# IMU-Measurement-and-Transmission-Module.net
KiCad netlist of a schematic drawn in EAGLE
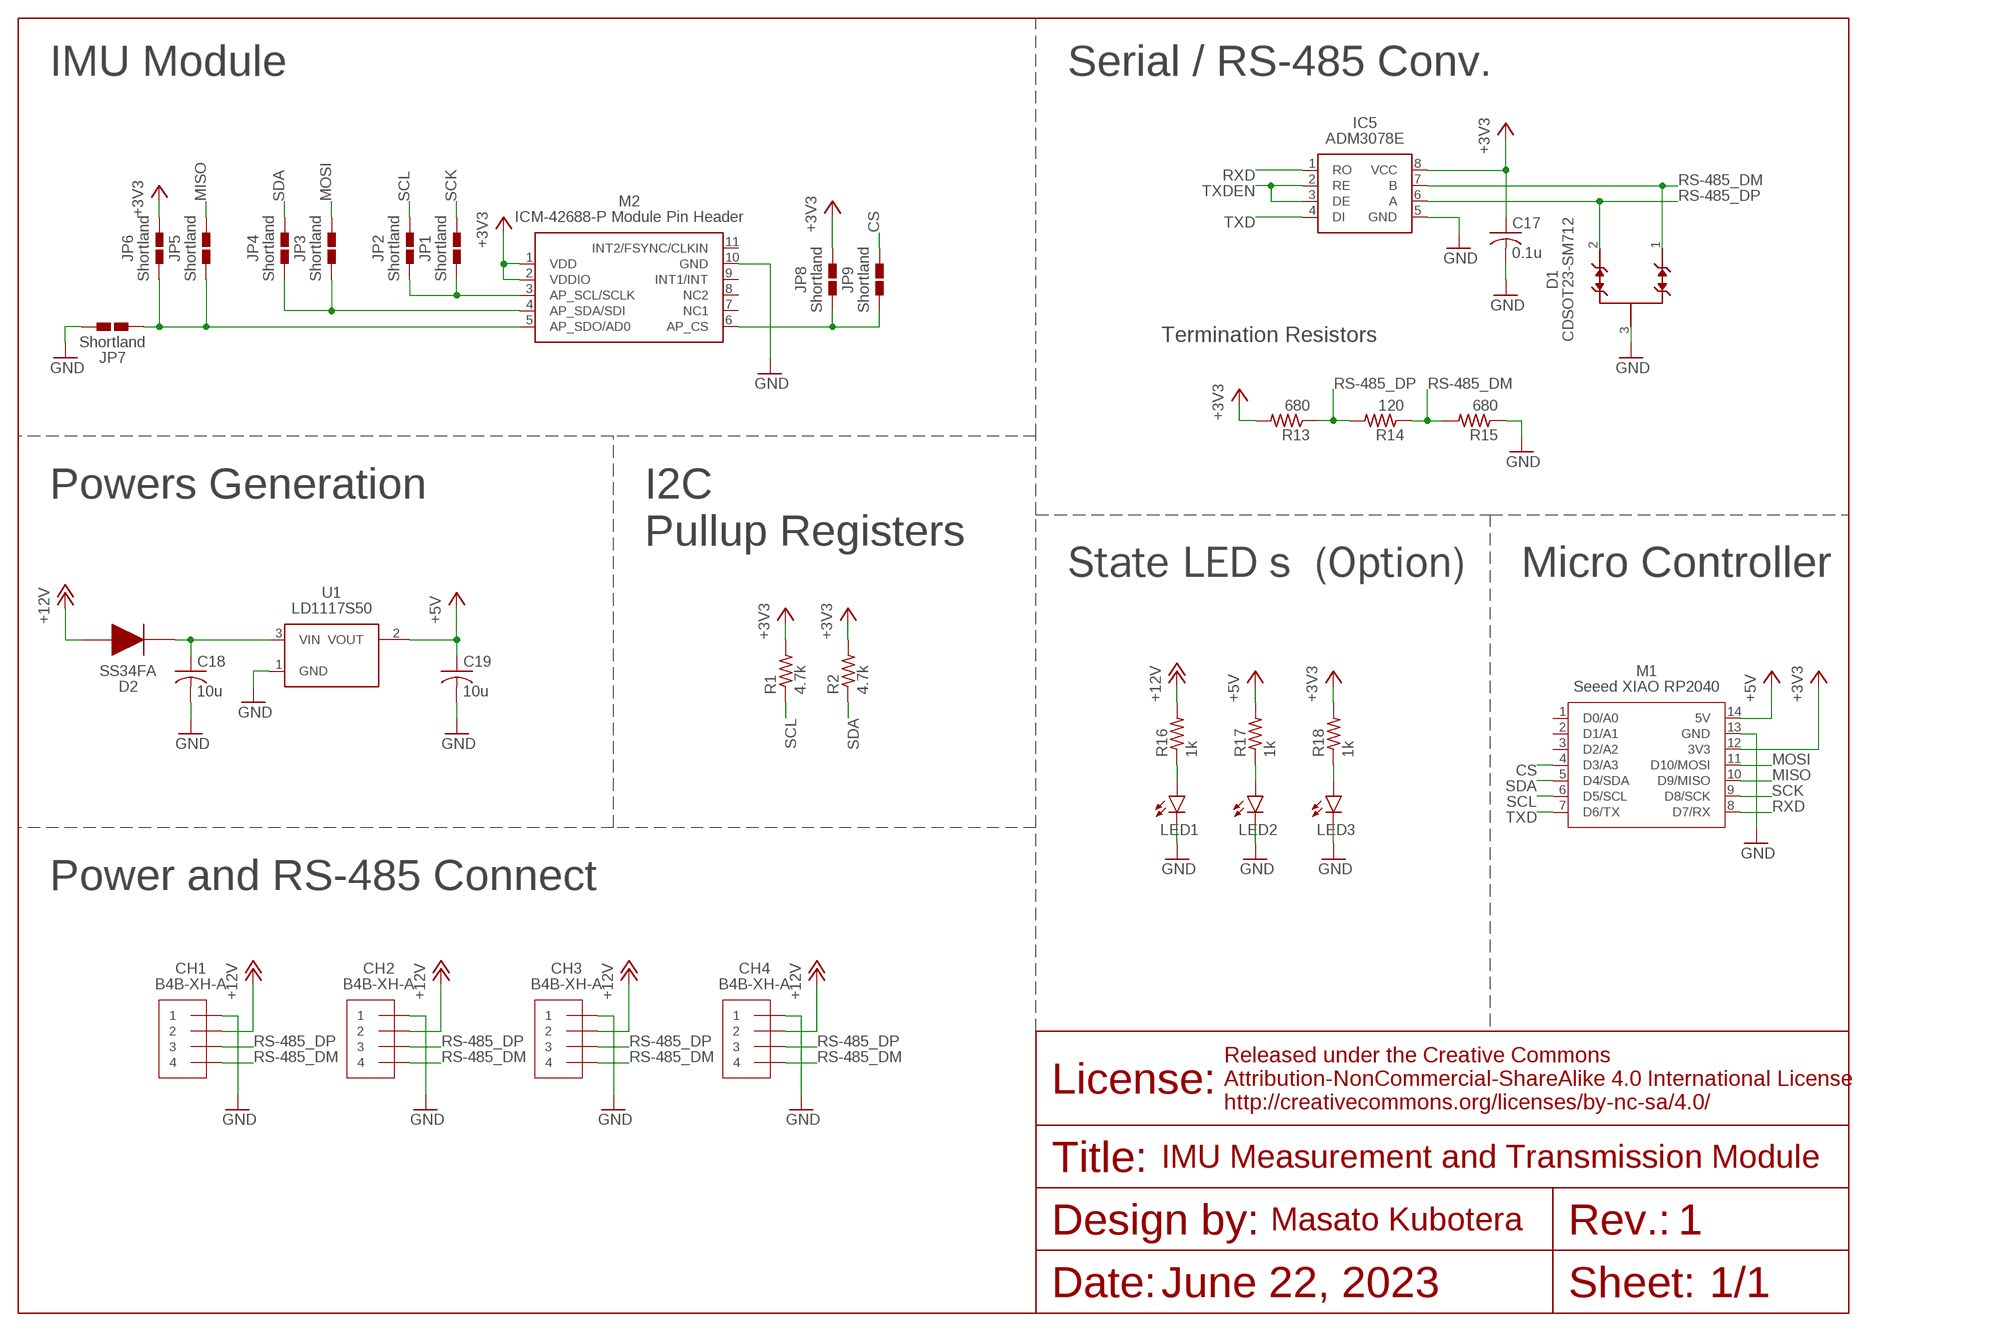
[diagram p0: schematic, sheet 1]

(export (version "E")
  (design (tool "Eeschema 10.0.6"))
  (components
    (comp (ref "C17")
      (value "0.1u")
      (footprint "eagle-import:C0603")
      (libsource (lib "eagle-import") (part "C-USC0603"))
    )
    (comp (ref "C18")
      (value "10u")
      (footprint "eagle-import:C0603")
      (libsource (lib "eagle-import") (part "C-USC0603"))
    )
    (comp (ref "C19")
      (value "10u")
      (footprint "eagle-import:C0603")
      (libsource (lib "eagle-import") (part "C-USC0603"))
    )
    (comp (ref "CH1")
      (value "B4B-XH-A")
      (footprint "eagle-import:B4B-XH-A")
      (libsource (lib "eagle-import") (part "B4B-XH-A"))
    )
    (comp (ref "CH2")
      (value "B4B-XH-A")
      (footprint "eagle-import:B4B-XH-A")
      (libsource (lib "eagle-import") (part "B4B-XH-A"))
    )
    (comp (ref "CH3")
      (value "B4B-XH-A")
      (footprint "eagle-import:B4B-XH-A")
      (libsource (lib "eagle-import") (part "B4B-XH-A"))
    )
    (comp (ref "CH4")
      (value "B4B-XH-A")
      (footprint "eagle-import:B4B-XH-A")
      (libsource (lib "eagle-import") (part "B4B-XH-A"))
    )
    (comp (ref "D1")
      (value "CDSOT23-SM712")
      (footprint "eagle-import:SOT-23-3")
      (libsource (lib "eagle-import") (part "CDSOT23-SM712"))
    )
    (comp (ref "D2")
      (value "SS34FA")
      (footprint "eagle-import:SS34FA")
      (libsource (lib "eagle-import") (part "SS34FA"))
    )
    (comp (ref "IC5")
      (value "ADM3078E")
      (footprint "eagle-import:ADM3078E")
      (libsource (lib "eagle-import") (part "ADM3078E"))
    )
    (comp (ref "JP1")
      (value "SHORTLAND")
      (footprint "eagle-import:SHORTLAND")
      (libsource (lib "eagle-import") (part "SHORTLAND"))
    )
    (comp (ref "JP2")
      (value "SHORTLAND")
      (footprint "eagle-import:SHORTLAND")
      (libsource (lib "eagle-import") (part "SHORTLAND"))
    )
    (comp (ref "JP3")
      (value "SHORTLAND")
      (footprint "eagle-import:SHORTLAND")
      (libsource (lib "eagle-import") (part "SHORTLAND"))
    )
    (comp (ref "JP4")
      (value "SHORTLAND")
      (footprint "eagle-import:SHORTLAND")
      (libsource (lib "eagle-import") (part "SHORTLAND"))
    )
    (comp (ref "JP5")
      (value "SHORTLAND")
      (footprint "eagle-import:SHORTLAND")
      (libsource (lib "eagle-import") (part "SHORTLAND"))
    )
    (comp (ref "JP6")
      (value "SHORTLAND")
      (footprint "eagle-import:SHORTLAND")
      (libsource (lib "eagle-import") (part "SHORTLAND"))
    )
    (comp (ref "JP7")
      (value "SHORTLAND")
      (footprint "eagle-import:SHORTLAND")
      (libsource (lib "eagle-import") (part "SHORTLAND"))
    )
    (comp (ref "JP8")
      (value "SHORTLAND")
      (footprint "eagle-import:SHORTLAND")
      (libsource (lib "eagle-import") (part "SHORTLAND"))
    )
    (comp (ref "JP9")
      (value "SHORTLAND")
      (footprint "eagle-import:SHORTLAND")
      (libsource (lib "eagle-import") (part "SHORTLAND"))
    )
    (comp (ref "LED1")
      (value "LEDSML0603")
      (footprint "eagle-import:SML0603")
      (libsource (lib "eagle-import") (part "LEDSML0603"))
    )
    (comp (ref "LED2")
      (value "LEDSML0603")
      (footprint "eagle-import:SML0603")
      (libsource (lib "eagle-import") (part "LEDSML0603"))
    )
    (comp (ref "LED3")
      (value "LEDSML0603")
      (footprint "eagle-import:SML0603")
      (libsource (lib "eagle-import") (part "LEDSML0603"))
    )
    (comp (ref "M1")
      (value "SEEED_XIAO_RP2040_HOLE")
      (footprint "eagle-import:SEEED_XIAO_HOLE")
      (libsource (lib "eagle-import") (part "SEEED_XIAO_RP2040_HOLE"))
    )
    (comp (ref "M2")
      (value "ICM-42688-P-MODULE-PINHEADER")
      (footprint "eagle-import:ICM-42688-P-MODULE-PINHEADER")
      (libsource (lib "eagle-import") (part "ICM-42688-P-MODULE-PINHEADER"))
    )
    (comp (ref "R1")
      (value "4.7k")
      (footprint "eagle-import:R0603")
      (libsource (lib "eagle-import") (part "R-US_R0603"))
    )
    (comp (ref "R2")
      (value "4.7k")
      (footprint "eagle-import:R0603")
      (libsource (lib "eagle-import") (part "R-US_R0603"))
    )
    (comp (ref "R13")
      (value "680")
      (footprint "eagle-import:R0603")
      (libsource (lib "eagle-import") (part "R-US_R0603"))
    )
    (comp (ref "R14")
      (value "120")
      (footprint "eagle-import:R0603")
      (libsource (lib "eagle-import") (part "R-US_R0603"))
    )
    (comp (ref "R15")
      (value "680")
      (footprint "eagle-import:R0603")
      (libsource (lib "eagle-import") (part "R-US_R0603"))
    )
    (comp (ref "R16")
      (value "1k")
      (footprint "eagle-import:R0603")
      (libsource (lib "eagle-import") (part "R-US_R0603"))
    )
    (comp (ref "R17")
      (value "1k")
      (footprint "eagle-import:R0603")
      (libsource (lib "eagle-import") (part "R-US_R0603"))
    )
    (comp (ref "R18")
      (value "1k")
      (footprint "eagle-import:R0603")
      (libsource (lib "eagle-import") (part "R-US_R0603"))
    )
    (comp (ref "U1")
      (value "LD1117S50")
      (footprint "eagle-import:SOT-223")
      (libsource (lib "eagle-import") (part "LD1117S50"))
    )
  )
  (nets
    (net (code "1") (name "+3V3") (class "Default")
      (node (ref "C17") (pin "1") (pinfunction "1_1") (pintype "passive"))
      (node (ref "IC5") (pin "8") (pinfunction "VCC_8") (pintype "bidirectional"))
      (node (ref "JP6") (pin "2") (pinfunction "2_2") (pintype "bidirectional"))
      (node (ref "JP8") (pin "2") (pinfunction "2_2") (pintype "bidirectional"))
      (node (ref "M1") (pin "12") (pinfunction "3V3_12") (pintype "bidirectional"))
      (node (ref "M2") (pin "1") (pinfunction "VDD_1") (pintype "bidirectional"))
      (node (ref "M2") (pin "2") (pinfunction "VDDIO_2") (pintype "bidirectional"))
      (node (ref "R1") (pin "2") (pinfunction "2_2") (pintype "passive"))
      (node (ref "R13") (pin "2") (pinfunction "2_2") (pintype "passive"))
      (node (ref "R18") (pin "2") (pinfunction "2_2") (pintype "passive"))
      (node (ref "R2") (pin "2") (pinfunction "2_2") (pintype "passive"))
    )
    (net (code "2") (name "+5V") (class "Default")
      (node (ref "C19") (pin "1") (pinfunction "1_1") (pintype "passive"))
      (node (ref "M1") (pin "14") (pinfunction "5V_14") (pintype "bidirectional"))
      (node (ref "R17") (pin "2") (pinfunction "2_2") (pintype "passive"))
      (node (ref "U1") (pin "2") (pinfunction "VOUT_2") (pintype "bidirectional"))
    )
    (net (code "3") (name "+12V") (class "Default")
      (node (ref "CH1") (pin "2") (pinfunction "2_2") (pintype "bidirectional"))
      (node (ref "CH2") (pin "2") (pinfunction "2_2") (pintype "bidirectional"))
      (node (ref "CH3") (pin "2") (pinfunction "2_2") (pintype "bidirectional"))
      (node (ref "CH4") (pin "2") (pinfunction "2_2") (pintype "bidirectional"))
      (node (ref "D2") (pin "2") (pinfunction "2_2") (pintype "bidirectional"))
      (node (ref "R16") (pin "2") (pinfunction "2_2") (pintype "passive"))
    )
    (net (code "4") (name "/CS") (class "Default")
      (node (ref "JP9") (pin "2") (pinfunction "2_2") (pintype "bidirectional"))
      (node (ref "M1") (pin "4") (pinfunction "D3/A3_4") (pintype "bidirectional"))
    )
    (net (code "5") (name "/MISO") (class "Default")
      (node (ref "JP5") (pin "2") (pinfunction "2_2") (pintype "bidirectional"))
      (node (ref "M1") (pin "10") (pinfunction "D9/MISO_10") (pintype "bidirectional"))
    )
    (net (code "6") (name "/MOSI") (class "Default")
      (node (ref "JP3") (pin "2") (pinfunction "2_2") (pintype "bidirectional"))
      (node (ref "M1") (pin "11") (pinfunction "D10/MOSI_11") (pintype "bidirectional"))
    )
    (net (code "7") (name "/RS-485_DM") (class "Default")
      (node (ref "CH1") (pin "4") (pinfunction "4_4") (pintype "bidirectional"))
      (node (ref "CH2") (pin "4") (pinfunction "4_4") (pintype "bidirectional"))
      (node (ref "CH3") (pin "4") (pinfunction "4_4") (pintype "bidirectional"))
      (node (ref "CH4") (pin "4") (pinfunction "4_4") (pintype "bidirectional"))
      (node (ref "D1") (pin "1") (pinfunction "1_1") (pintype "bidirectional"))
      (node (ref "IC5") (pin "7") (pinfunction "B_7") (pintype "bidirectional"))
      (node (ref "R14") (pin "1") (pinfunction "1_1") (pintype "passive"))
      (node (ref "R15") (pin "2") (pinfunction "2_2") (pintype "passive"))
    )
    (net (code "8") (name "/RS-485_DP") (class "Default")
      (node (ref "CH1") (pin "3") (pinfunction "3_3") (pintype "bidirectional"))
      (node (ref "CH2") (pin "3") (pinfunction "3_3") (pintype "bidirectional"))
      (node (ref "CH3") (pin "3") (pinfunction "3_3") (pintype "bidirectional"))
      (node (ref "CH4") (pin "3") (pinfunction "3_3") (pintype "bidirectional"))
      (node (ref "D1") (pin "2") (pinfunction "2_2") (pintype "bidirectional"))
      (node (ref "IC5") (pin "6") (pinfunction "A_6") (pintype "bidirectional"))
      (node (ref "R13") (pin "1") (pinfunction "1_1") (pintype "passive"))
      (node (ref "R14") (pin "2") (pinfunction "2_2") (pintype "passive"))
    )
    (net (code "9") (name "/RXD") (class "Default")
      (node (ref "IC5") (pin "1") (pinfunction "RO_1") (pintype "bidirectional"))
      (node (ref "M1") (pin "8") (pinfunction "D7/RX_8") (pintype "bidirectional"))
    )
    (net (code "10") (name "/SCK") (class "Default")
      (node (ref "JP1") (pin "2") (pinfunction "2_2") (pintype "bidirectional"))
      (node (ref "M1") (pin "9") (pinfunction "D8/SCK_9") (pintype "bidirectional"))
    )
    (net (code "11") (name "/SCL") (class "Default")
      (node (ref "JP2") (pin "2") (pinfunction "2_2") (pintype "bidirectional"))
      (node (ref "M1") (pin "6") (pinfunction "D5/SCL_6") (pintype "bidirectional"))
      (node (ref "R1") (pin "1") (pinfunction "1_1") (pintype "passive"))
    )
    (net (code "12") (name "/SDA") (class "Default")
      (node (ref "JP4") (pin "2") (pinfunction "2_2") (pintype "bidirectional"))
      (node (ref "M1") (pin "5") (pinfunction "D4/SDA_5") (pintype "bidirectional"))
      (node (ref "R2") (pin "1") (pinfunction "1_1") (pintype "passive"))
    )
    (net (code "13") (name "/TXD") (class "Default")
      (node (ref "IC5") (pin "4") (pinfunction "DI_4") (pintype "bidirectional"))
      (node (ref "M1") (pin "7") (pinfunction "D6/TX_7") (pintype "bidirectional"))
    )
    (net (code "14") (name "/TXDEN") (class "Default")
      (node (ref "IC5") (pin "2") (pinfunction "RE_2") (pintype "bidirectional"))
      (node (ref "IC5") (pin "3") (pinfunction "DE_3") (pintype "bidirectional"))
    )
    (net (code "15") (name "GND") (class "Default")
      (node (ref "C17") (pin "2") (pinfunction "2_2") (pintype "passive"))
      (node (ref "C18") (pin "2") (pinfunction "2_2") (pintype "passive"))
      (node (ref "C19") (pin "2") (pinfunction "2_2") (pintype "passive"))
      (node (ref "CH1") (pin "1") (pinfunction "1_1") (pintype "bidirectional"))
      (node (ref "CH2") (pin "1") (pinfunction "1_1") (pintype "bidirectional"))
      (node (ref "CH3") (pin "1") (pinfunction "1_1") (pintype "bidirectional"))
      (node (ref "CH4") (pin "1") (pinfunction "1_1") (pintype "bidirectional"))
      (node (ref "D1") (pin "3") (pinfunction "3_3") (pintype "bidirectional"))
      (node (ref "IC5") (pin "5") (pinfunction "GND_5") (pintype "bidirectional"))
      (node (ref "JP7") (pin "2") (pinfunction "2_2") (pintype "bidirectional"))
      (node (ref "LED1") (pin "C") (pinfunction "C_C") (pintype "passive"))
      (node (ref "LED2") (pin "C") (pinfunction "C_C") (pintype "passive"))
      (node (ref "LED3") (pin "C") (pinfunction "C_C") (pintype "passive"))
      (node (ref "M1") (pin "13") (pinfunction "GND_13") (pintype "bidirectional"))
      (node (ref "M2") (pin "10") (pinfunction "GND_10") (pintype "bidirectional"))
      (node (ref "R15") (pin "1") (pinfunction "1_1") (pintype "passive"))
      (node (ref "U1") (pin "1") (pinfunction "GND_1") (pintype "bidirectional"))
    )
    (net (code "16") (name "Net-(LED1-PadA)") (class "Default")
      (node (ref "LED1") (pin "A") (pinfunction "A_A") (pintype "passive"))
      (node (ref "R16") (pin "1") (pinfunction "1_1") (pintype "passive"))
    )
    (net (code "17") (name "Net-(LED2-PadA)") (class "Default")
      (node (ref "LED2") (pin "A") (pinfunction "A_A") (pintype "passive"))
      (node (ref "R17") (pin "1") (pinfunction "1_1") (pintype "passive"))
    )
    (net (code "18") (name "Net-(LED3-PadA)") (class "Default")
      (node (ref "LED3") (pin "A") (pinfunction "A_A") (pintype "passive"))
      (node (ref "R18") (pin "1") (pinfunction "1_1") (pintype "passive"))
    )
    (net (code "19") (name "Net-(M2-AP_CS)") (class "Default")
      (node (ref "JP8") (pin "1") (pinfunction "1_1") (pintype "bidirectional"))
      (node (ref "JP9") (pin "1") (pinfunction "1_1") (pintype "bidirectional"))
      (node (ref "M2") (pin "6") (pinfunction "AP_CS_6") (pintype "bidirectional"))
    )
    (net (code "20") (name "Net-(M2-AP_SCL{slash}SCLK)") (class "Default")
      (node (ref "JP1") (pin "1") (pinfunction "1_1") (pintype "bidirectional"))
      (node (ref "JP2") (pin "1") (pinfunction "1_1") (pintype "bidirectional"))
      (node (ref "M2") (pin "3") (pinfunction "AP_SCL/SCLK_3") (pintype "bidirectional"))
    )
    (net (code "21") (name "Net-(M2-AP_SDA{slash}SDI)") (class "Default")
      (node (ref "JP3") (pin "1") (pinfunction "1_1") (pintype "bidirectional"))
      (node (ref "JP4") (pin "1") (pinfunction "1_1") (pintype "bidirectional"))
      (node (ref "M2") (pin "4") (pinfunction "AP_SDA/SDI_4") (pintype "bidirectional"))
    )
    (net (code "22") (name "Net-(M2-AP_SDO{slash}AD0)") (class "Default")
      (node (ref "JP5") (pin "1") (pinfunction "1_1") (pintype "bidirectional"))
      (node (ref "JP6") (pin "1") (pinfunction "1_1") (pintype "bidirectional"))
      (node (ref "JP7") (pin "1") (pinfunction "1_1") (pintype "bidirectional"))
      (node (ref "M2") (pin "5") (pinfunction "AP_SDO/AD0_5") (pintype "bidirectional"))
    )
    (net (code "23") (name "Net-(U1-VIN)") (class "Default")
      (node (ref "C18") (pin "1") (pinfunction "1_1") (pintype "passive"))
      (node (ref "D2") (pin "1") (pinfunction "1_1") (pintype "bidirectional"))
      (node (ref "U1") (pin "3") (pinfunction "VIN_3") (pintype "bidirectional"))
    )
    (net (code "24") (name "unconnected-(M1-D0{slash}A0-Pad1)") (class "Default")
      (node (ref "M1") (pin "1") (pinfunction "D0/A0_1") (pintype "bidirectional"))
    )
    (net (code "25") (name "unconnected-(M1-D1{slash}A1-Pad2)") (class "Default")
      (node (ref "M1") (pin "2") (pinfunction "D1/A1_2") (pintype "bidirectional"))
    )
    (net (code "26") (name "unconnected-(M1-D2{slash}A2-Pad3)") (class "Default")
      (node (ref "M1") (pin "3") (pinfunction "D2/A2_3") (pintype "bidirectional"))
    )
    (net (code "27") (name "unconnected-(M2-INT1{slash}INT-Pad9)") (class "Default")
      (node (ref "M2") (pin "9") (pinfunction "INT1/INT_9") (pintype "bidirectional"))
    )
    (net (code "28") (name "unconnected-(M2-INT2{slash}FSYNC{slash}CLKIN-Pad11)") (class "Default")
      (node (ref "M2") (pin "11") (pinfunction "INT2/FSYNC/CLKIN_11") (pintype "bidirectional"))
    )
    (net (code "29") (name "unconnected-(M2-NC1-Pad7)") (class "Default")
      (node (ref "M2") (pin "7") (pinfunction "NC1_7") (pintype "no_connect"))
    )
    (net (code "30") (name "unconnected-(M2-NC2-Pad8)") (class "Default")
      (node (ref "M2") (pin "8") (pinfunction "NC2_8") (pintype "no_connect"))
    )
  )
)
